# WifiNode_Cpu0_R00.net
KiCad netlist of a schematic drawn in Altium Designer
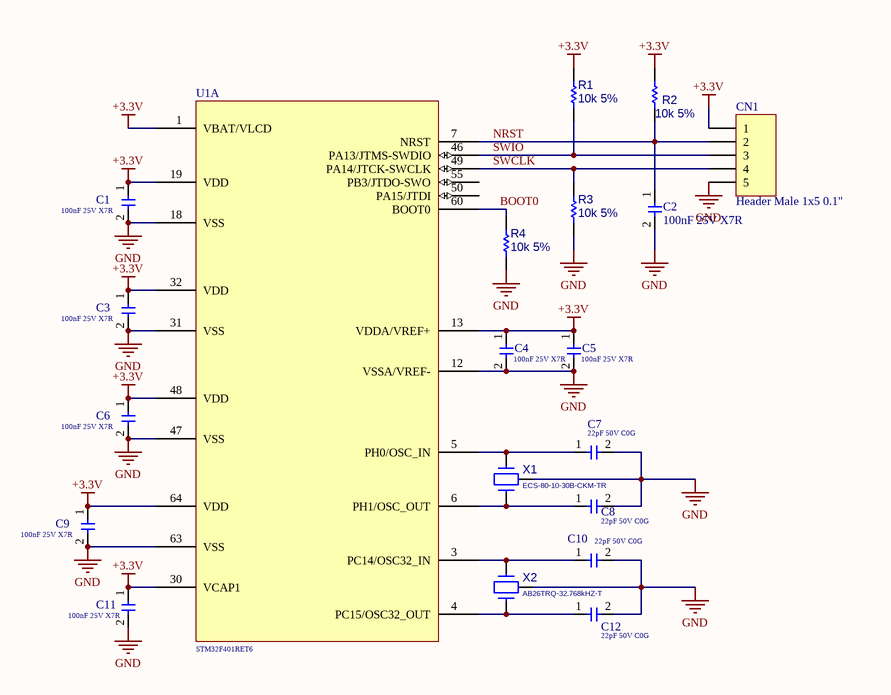
[diagram p0: WifiNode_Cpu0_R00.SchDoc]

(export (version "E")
  (design (tool "Eeschema 10.0.6"))
  (components
    (comp (ref "C1")
      (value "100nF 25V X7R")
      (footprint "C_0805")
      (description "Not polarized capacitor")
      (libsource (lib "IDCI_TP1_SFARA") (part "CAP_NP"))
    )
    (comp (ref "C2")
      (value "100nF 25V X7R")
      (footprint "C_0805")
      (description "Not polarized capacitor")
      (libsource (lib "IDCI_TP1_SFARA") (part "CAP_NP"))
    )
    (comp (ref "C3")
      (value "100nF 25V X7R")
      (footprint "C_0805")
      (description "Not polarized capacitor")
      (libsource (lib "IDCI_TP1_SFARA") (part "CAP_NP"))
    )
    (comp (ref "C4")
      (value "100nF 25V X7R")
      (footprint "C_0805")
      (description "Not polarized capacitor")
      (libsource (lib "IDCI_TP1_SFARA") (part "CAP_NP"))
    )
    (comp (ref "C5")
      (value "100nF 25V X7R")
      (footprint "C_0805")
      (description "Not polarized capacitor")
      (libsource (lib "IDCI_TP1_SFARA") (part "CAP_NP"))
    )
    (comp (ref "C6")
      (value "100nF 25V X7R")
      (footprint "C_0805")
      (description "Not polarized capacitor")
      (libsource (lib "IDCI_TP1_SFARA") (part "CAP_NP"))
    )
    (comp (ref "C7")
      (value "22pF 50V C0G")
      (footprint "C_0805")
      (description "Not polarized capacitor")
      (libsource (lib "IDCI_TP1_SFARA") (part "CAP_NP"))
    )
    (comp (ref "C8")
      (value "22pF 50V C0G")
      (footprint "C_0805")
      (description "Not polarized capacitor")
      (libsource (lib "IDCI_TP1_SFARA") (part "CAP_NP"))
    )
    (comp (ref "C9")
      (value "100nF 25V X7R")
      (footprint "C_0805")
      (description "Not polarized capacitor")
      (libsource (lib "IDCI_TP1_SFARA") (part "CAP_NP"))
    )
    (comp (ref "C10")
      (value "22pF 50V C0G")
      (footprint "C_0805")
      (description "Not polarized capacitor")
      (libsource (lib "IDCI_TP1_SFARA") (part "CAP_NP"))
    )
    (comp (ref "C11")
      (value "100nF 25V X7R")
      (footprint "C_0805")
      (description "Not polarized capacitor")
      (libsource (lib "IDCI_TP1_SFARA") (part "CAP_NP"))
    )
    (comp (ref "C12")
      (value "22pF 50V C0G")
      (footprint "C_0805")
      (description "Not polarized capacitor")
      (libsource (lib "IDCI_TP1_SFARA") (part "CAP_NP"))
    )
    (comp (ref "CN1")
      (value "Header Male 1x5 0.1\"")
      (footprint "Header_M_1x5_0.1\"")
      (description "Connector Generic 5 Vias")
      (libsource (lib "IDCI_TP1_SFARA") (part "CONN_05P"))
    )
    (comp (ref "R1")
      (value "10k 5%")
      (footprint "R_0805")
      (description "Resistor")
      (libsource (lib "IDCI_TP1_SFARA") (part "Res1"))
    )
    (comp (ref "R2")
      (value "10k 5%")
      (footprint "R_0805")
      (description "Resistor")
      (libsource (lib "IDCI_TP1_SFARA") (part "Res1"))
    )
    (comp (ref "R3")
      (value "10k 5%")
      (footprint "R_0805")
      (description "Resistor")
      (libsource (lib "IDCI_TP1_SFARA") (part "Res1"))
    )
    (comp (ref "R4")
      (value "10k 5%")
      (footprint "R_0805")
      (description "Resistor")
      (libsource (lib "IDCI_TP1_SFARA") (part "Res1"))
    )
    (comp (ref "U1")
      (value "STM32F401RET6")
      (footprint "LQFP_64")
      (libsource (lib "IDCI_TP1_SFARA") (part "STM32F401RE"))
    )
    (comp (ref "X1")
      (value "ECS-80-10-30B-CKM-TR")
      (footprint "ABM3C")
      (description "Crystal 2 Vias + GND")
      (libsource (lib "IDCI_TP1_SFARA") (part "CRYSTAL 3P"))
    )
    (comp (ref "X2")
      (value "AB26TRQ-32.768kHZ-T")
      (footprint "AB26TQF")
      (description "Crystal 2 Vias + GND")
      (libsource (lib "IDCI_TP1_SFARA") (part "CRYSTAL 3P"))
    )
  )
  (nets
    (net (code "1") (name "+3.3V") (class "Default")
      (node (ref "C1") (pin "1") (pintype "passive"))
      (node (ref "C11") (pin "1") (pintype "passive"))
      (node (ref "C3") (pin "1") (pintype "passive"))
      (node (ref "C4") (pin "1") (pintype "passive"))
      (node (ref "C5") (pin "1") (pintype "passive"))
      (node (ref "C6") (pin "1") (pintype "passive"))
      (node (ref "C9") (pin "1") (pintype "passive"))
      (node (ref "CN1") (pin "1") (pinfunction "1_1") (pintype "passive"))
      (node (ref "R1") (pin "2") (pinfunction "2_2") (pintype "passive"))
      (node (ref "R2") (pin "2") (pinfunction "2_2") (pintype "passive"))
      (node (ref "U1") (pin "1") (pinfunction "VBAT/VLCD_1") (pintype "passive"))
      (node (ref "U1") (pin "13") (pinfunction "VDDA/VREF+_13") (pintype "passive"))
      (node (ref "U1") (pin "19") (pinfunction "VDD_19") (pintype "passive"))
      (node (ref "U1") (pin "30") (pinfunction "VCAP1_30") (pintype "passive"))
      (node (ref "U1") (pin "32") (pinfunction "VDD_32") (pintype "passive"))
      (node (ref "U1") (pin "48") (pinfunction "VDD_48") (pintype "passive"))
      (node (ref "U1") (pin "64") (pinfunction "VDD_64") (pintype "passive"))
    )
    (net (code "2") (name "/BOOT0") (class "Default")
      (node (ref "R4") (pin "2") (pinfunction "2_2") (pintype "passive"))
      (node (ref "U1") (pin "60") (pinfunction "BOOT0_60") (pintype "passive"))
    )
    (net (code "3") (name "/NRST") (class "Default")
      (node (ref "C2") (pin "1") (pintype "passive"))
      (node (ref "CN1") (pin "2") (pinfunction "2_2") (pintype "passive"))
      (node (ref "R2") (pin "1") (pinfunction "1_1") (pintype "passive"))
      (node (ref "U1") (pin "7") (pinfunction "NRST_7") (pintype "passive"))
    )
    (net (code "4") (name "/SWCLK") (class "Default")
      (node (ref "CN1") (pin "4") (pinfunction "4_4") (pintype "passive"))
      (node (ref "R3") (pin "2") (pinfunction "2_2") (pintype "passive"))
      (node (ref "U1") (pin "49") (pinfunction "PA14/JTCK-SWCLK_49") (pintype "bidirectional"))
    )
    (net (code "5") (name "/SWIO") (class "Default")
      (node (ref "CN1") (pin "3") (pinfunction "3_3") (pintype "passive"))
      (node (ref "R1") (pin "1") (pinfunction "1_1") (pintype "passive"))
      (node (ref "U1") (pin "46") (pinfunction "PA13/JTMS-SWDIO_46") (pintype "bidirectional"))
    )
    (net (code "6") (name "GND") (class "Default")
      (node (ref "C1") (pin "2") (pintype "passive"))
      (node (ref "C10") (pin "2") (pintype "passive"))
      (node (ref "C11") (pin "2") (pintype "passive"))
      (node (ref "C12") (pin "2") (pintype "passive"))
      (node (ref "C2") (pin "2") (pintype "passive"))
      (node (ref "C3") (pin "2") (pintype "passive"))
      (node (ref "C4") (pin "2") (pintype "passive"))
      (node (ref "C5") (pin "2") (pintype "passive"))
      (node (ref "C6") (pin "2") (pintype "passive"))
      (node (ref "C7") (pin "2") (pintype "passive"))
      (node (ref "C8") (pin "2") (pintype "passive"))
      (node (ref "C9") (pin "2") (pintype "passive"))
      (node (ref "CN1") (pin "5") (pinfunction "5_5") (pintype "passive"))
      (node (ref "R3") (pin "1") (pinfunction "1_1") (pintype "passive"))
      (node (ref "R4") (pin "1") (pinfunction "1_1") (pintype "passive"))
      (node (ref "U1") (pin "12") (pinfunction "VSSA/VREF-_12") (pintype "passive"))
      (node (ref "U1") (pin "18") (pinfunction "VSS_18") (pintype "passive"))
      (node (ref "U1") (pin "31") (pinfunction "VSS_31") (pintype "passive"))
      (node (ref "U1") (pin "47") (pinfunction "VSS_47") (pintype "passive"))
      (node (ref "U1") (pin "63") (pinfunction "VSS_63") (pintype "passive"))
      (node (ref "X1") (pin "3") (pinfunction "3_3") (pintype "passive"))
      (node (ref "X2") (pin "3") (pinfunction "3_3") (pintype "passive"))
    )
    (net (code "7") (name "Net-(U1A-PC14{slash}OSC32_IN)") (class "Default")
      (node (ref "C10") (pin "1") (pintype "passive"))
      (node (ref "U1") (pin "3") (pinfunction "PC14/OSC32_IN_3") (pintype "passive"))
      (node (ref "X2") (pin "2") (pinfunction "2_2") (pintype "passive"))
    )
    (net (code "8") (name "Net-(U1A-PC15{slash}OSC32_OUT)") (class "Default")
      (node (ref "C12") (pin "1") (pintype "passive"))
      (node (ref "U1") (pin "4") (pinfunction "PC15/OSC32_OUT_4") (pintype "passive"))
      (node (ref "X2") (pin "1") (pinfunction "1_1") (pintype "passive"))
    )
    (net (code "9") (name "Net-(U1A-PH0{slash}OSC_IN)") (class "Default")
      (node (ref "C7") (pin "1") (pintype "passive"))
      (node (ref "U1") (pin "5") (pinfunction "PH0/OSC_IN_5") (pintype "passive"))
      (node (ref "X1") (pin "2") (pinfunction "2_2") (pintype "passive"))
    )
    (net (code "10") (name "Net-(U1A-PH1{slash}OSC_OUT)") (class "Default")
      (node (ref "C8") (pin "1") (pintype "passive"))
      (node (ref "U1") (pin "6") (pinfunction "PH1/OSC_OUT_6") (pintype "passive"))
      (node (ref "X1") (pin "1") (pinfunction "1_1") (pintype "passive"))
    )
    (net (code "11") (name "unconnected-(U1A-PA15{slash}JTDI-Pad50)") (class "Default")
      (node (ref "U1") (pin "50") (pinfunction "PA15/JTDI_50") (pintype "bidirectional"))
    )
    (net (code "12") (name "unconnected-(U1A-PB3{slash}JTDO-SWO-Pad55)") (class "Default")
      (node (ref "U1") (pin "55") (pinfunction "PB3/JTDO-SWO_55") (pintype "bidirectional"))
    )
  )
)
